# PWR.net
KiCad netlist of a schematic drawn in Altium Designer
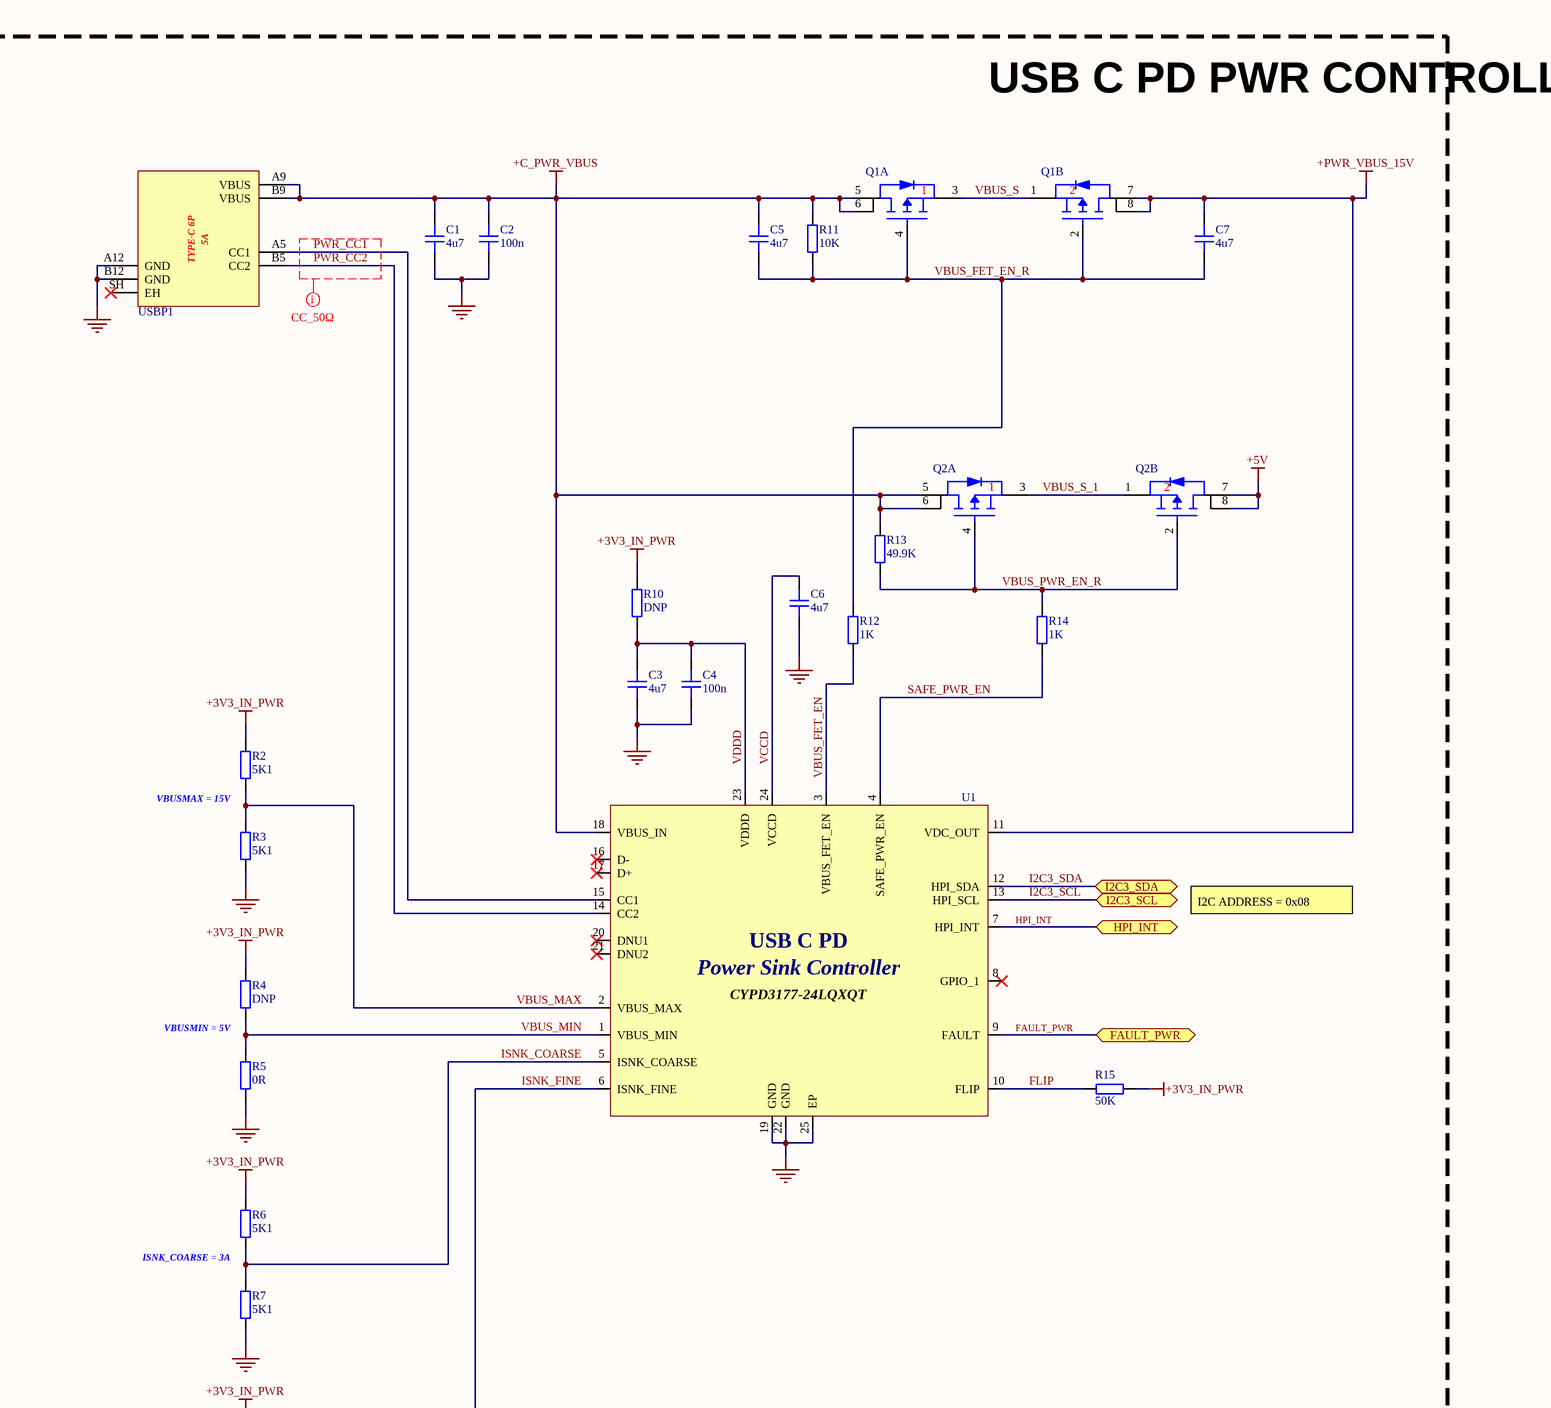
[diagram p0: PWR.SchDoc, top left]
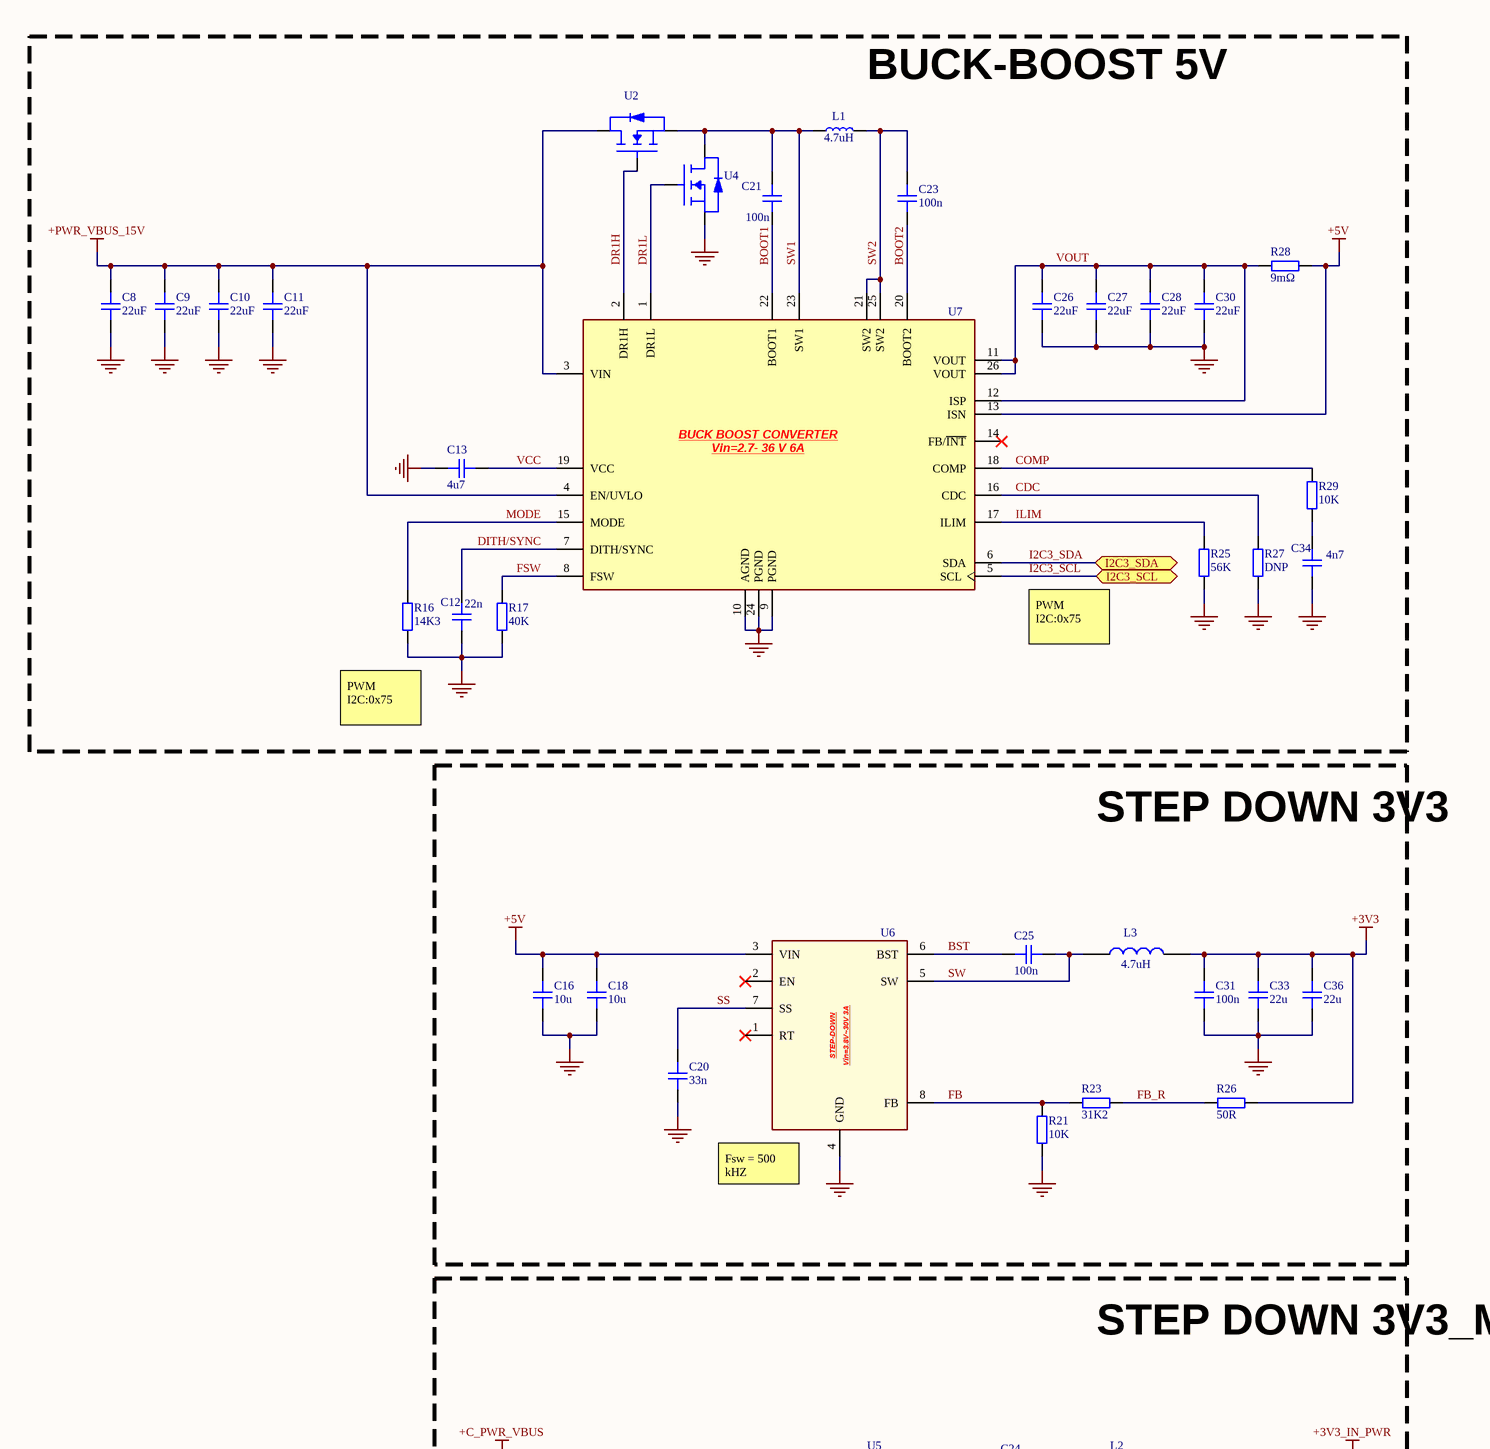
[diagram p1: PWR.SchDoc, top right]
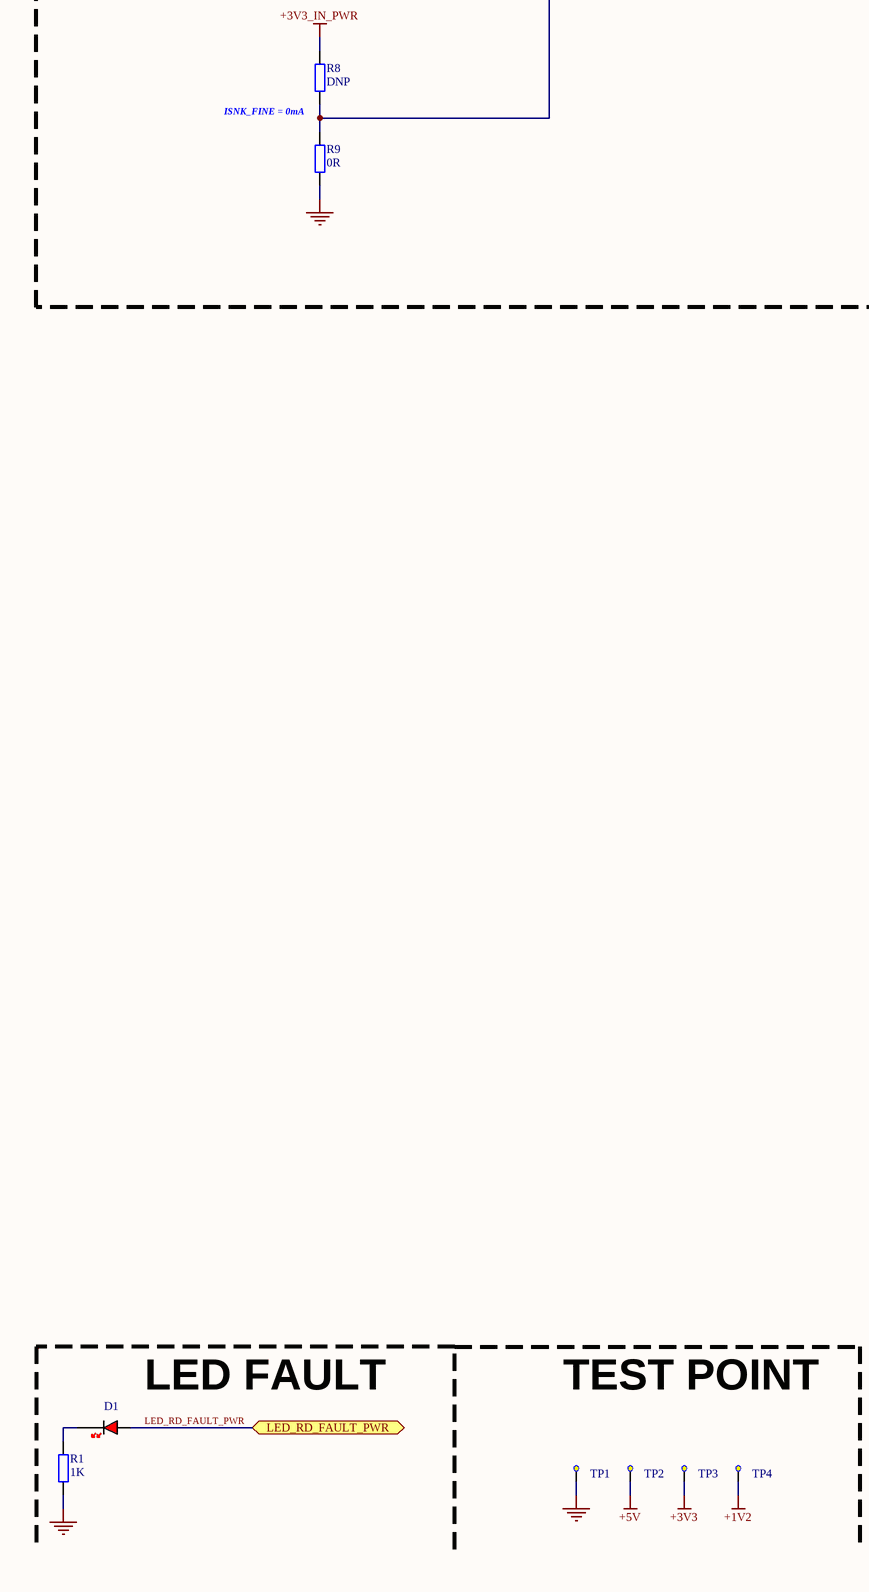
[diagram p2: PWR.SchDoc, bottom left]
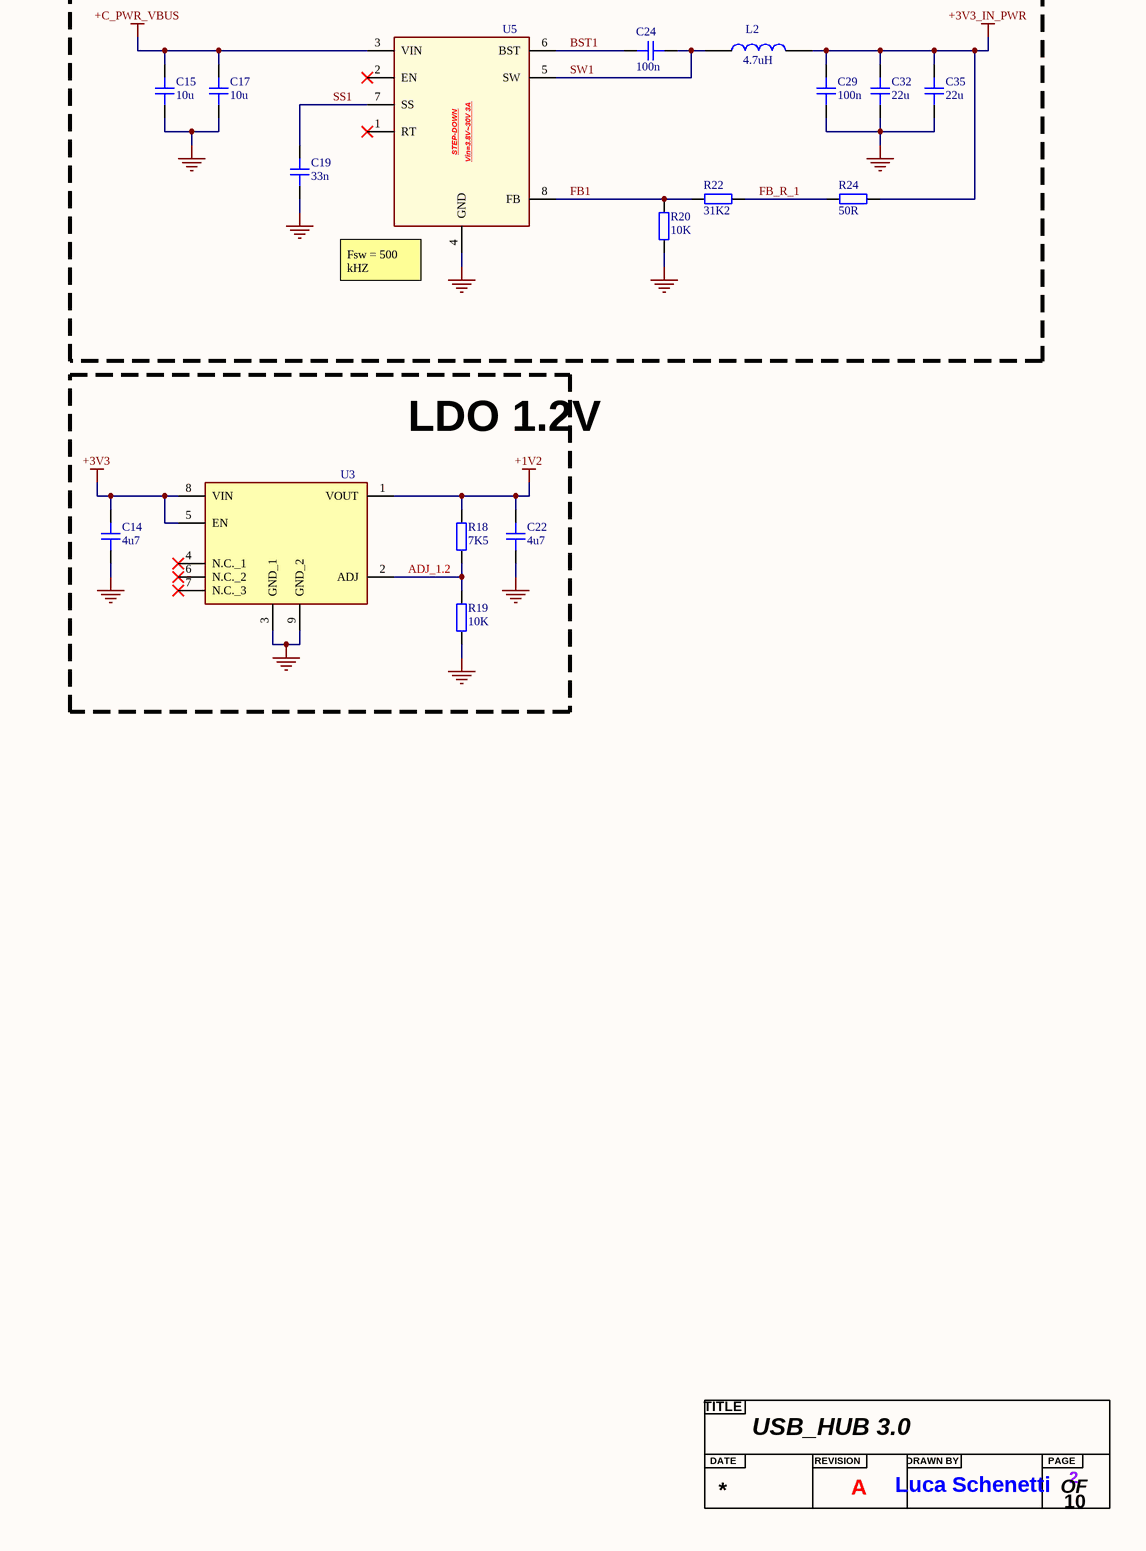
[diagram p3: PWR.SchDoc, bottom right]

(export (version "E")
  (design (tool "Eeschema 10.0.6"))
  (components
    (comp (ref "C1")
      (value "4u7")
      (footprint "CAP_0805")
      (description "[C1779]")
      (libsource (lib "Schematic-Lib-PhilsLab") (part "CAP_0805"))
    )
    (comp (ref "C2")
      (value "100n")
      (footprint "CAP_0603")
      (description "[C14663]")
      (libsource (lib "Schematic-Lib-PhilsLab") (part "CAP_0603"))
    )
    (comp (ref "C3")
      (value "4u7")
      (footprint "CAP_0603")
      (description "[C19666]")
      (libsource (lib "Schematic-Lib-PhilsLab") (part "CAP_0603"))
    )
    (comp (ref "C4")
      (value "100n")
      (footprint "CAP_0603")
      (description "[C14663]")
      (libsource (lib "Schematic-Lib-PhilsLab") (part "CAP_0603"))
    )
    (comp (ref "C5")
      (value "4u7")
      (footprint "CAP_0805")
      (description "[C1779]")
      (libsource (lib "Schematic-Lib-PhilsLab") (part "CAP_0805"))
    )
    (comp (ref "C6")
      (value "4u7")
      (footprint "CAP_0603")
      (description "[C69335]")
      (libsource (lib "Schematic-Lib-PhilsLab") (part "CAP_0603"))
    )
    (comp (ref "C7")
      (value "4u7")
      (footprint "CAP_0805")
      (description "[C1779]")
      (libsource (lib "Schematic-Lib-PhilsLab") (part "CAP_0805"))
    )
    (comp (ref "C8")
      (value "22uF")
      (footprint "CAP_0805")
      (description "[C45783]")
      (libsource (lib "Schematic-Lib-PhilsLab") (part "CAP_0805"))
    )
    (comp (ref "C9")
      (value "22uF")
      (footprint "CAP_0805")
      (description "[C45783]")
      (libsource (lib "Schematic-Lib-PhilsLab") (part "CAP_0805"))
    )
    (comp (ref "C10")
      (value "22uF")
      (footprint "CAP_0805")
      (description "[C45783]")
      (libsource (lib "Schematic-Lib-PhilsLab") (part "CAP_0805"))
    )
    (comp (ref "C11")
      (value "22uF")
      (footprint "CAP_0805")
      (description "[C45783]")
      (libsource (lib "Schematic-Lib-PhilsLab") (part "CAP_0805"))
    )
    (comp (ref "C12")
      (value "22n")
      (footprint "CAP_0603")
      (description "[C21122]")
      (libsource (lib "Schematic-Lib-PhilsLab") (part "CAP_0603"))
    )
    (comp (ref "C13")
      (value "4u7")
      (footprint "CAP_0603")
      (description "[C19666]")
      (libsource (lib "Schematic-Lib-PhilsLab") (part "CAP_0603"))
    )
    (comp (ref "C14")
      (value "4u7")
      (footprint "CAP_0603")
      (description "[C19666]")
      (libsource (lib "Schematic-Lib-PhilsLab") (part "CAP_0603"))
    )
    (comp (ref "C15")
      (value "10u")
      (footprint "CAP_0805")
      (description "Capacitor SMD 0805[C440198]")
      (libsource (lib "Schematic-Lib-PhilsLab") (part "CAP_0805"))
    )
    (comp (ref "C16")
      (value "10u")
      (footprint "CAP_0805")
      (description "Capacitor SMD 0805[C440198]")
      (libsource (lib "Schematic-Lib-PhilsLab") (part "CAP_0805"))
    )
    (comp (ref "C17")
      (value "10u")
      (footprint "CAP_0805")
      (description "Capacitor SMD 0805[C440198]")
      (libsource (lib "Schematic-Lib-PhilsLab") (part "CAP_0805"))
    )
    (comp (ref "C18")
      (value "10u")
      (footprint "CAP_0805")
      (description "Capacitor SMD 0805[C440198]")
      (libsource (lib "Schematic-Lib-PhilsLab") (part "CAP_0805"))
    )
    (comp (ref "C19")
      (value "33n")
      (footprint "CAP_0603")
      (description "[C21117]")
      (libsource (lib "Schematic-Lib-PhilsLab") (part "CAP_0603"))
    )
    (comp (ref "C20")
      (value "33n")
      (footprint "CAP_0603")
      (description "[C21117]")
      (libsource (lib "Schematic-Lib-PhilsLab") (part "CAP_0603"))
    )
    (comp (ref "C21")
      (value "100n")
      (footprint "CAP_0603")
      (description "[C14663]")
      (libsource (lib "Schematic-Lib-PhilsLab") (part "CAP_0603"))
    )
    (comp (ref "C22")
      (value "4u7")
      (footprint "CAP_0603")
      (description "[C19666]")
      (libsource (lib "Schematic-Lib-PhilsLab") (part "CAP_0603"))
    )
    (comp (ref "C23")
      (value "100n")
      (footprint "CAP_0603")
      (description "[C14663]")
      (libsource (lib "Schematic-Lib-PhilsLab") (part "CAP_0603"))
    )
    (comp (ref "C24")
      (value "100n")
      (footprint "CAP_0603")
      (description "Capacitor SMD 0603 [C14663]")
      (libsource (lib "Schematic-Lib-PhilsLab") (part "CAP_0603"))
    )
    (comp (ref "C25")
      (value "100n")
      (footprint "CAP_0603")
      (description "Capacitor SMD 0603 [C14663]")
      (libsource (lib "Schematic-Lib-PhilsLab") (part "CAP_0603"))
    )
    (comp (ref "C26")
      (value "22uF")
      (footprint "CAP_0805")
      (description "[C45783]")
      (libsource (lib "Schematic-Lib-PhilsLab") (part "CAP_0805"))
    )
    (comp (ref "C27")
      (value "22uF")
      (footprint "CAP_0805")
      (description "[C45783]")
      (libsource (lib "Schematic-Lib-PhilsLab") (part "CAP_0805"))
    )
    (comp (ref "C28")
      (value "22uF")
      (footprint "CAP_0805")
      (description "[C45783]")
      (libsource (lib "Schematic-Lib-PhilsLab") (part "CAP_0805"))
    )
    (comp (ref "C29")
      (value "100n")
      (footprint "CAP_0603")
      (description "Capacitor SMD 0603 [C14663]")
      (libsource (lib "Schematic-Lib-PhilsLab") (part "CAP_0603"))
    )
    (comp (ref "C30")
      (value "22uF")
      (footprint "CAP_0805")
      (description "[C45783]")
      (libsource (lib "Schematic-Lib-PhilsLab") (part "CAP_0805"))
    )
    (comp (ref "C31")
      (value "100n")
      (footprint "CAP_0603")
      (description "Capacitor SMD 0603 [C14663]")
      (libsource (lib "Schematic-Lib-PhilsLab") (part "CAP_0603"))
    )
    (comp (ref "C32")
      (value "22u")
      (footprint "CAP_0603")
      (description "Capacitor SMD 0603 [C59461]")
      (libsource (lib "Schematic-Lib-PhilsLab") (part "CAP_0603"))
    )
    (comp (ref "C33")
      (value "22u")
      (footprint "CAP_0603")
      (description "Capacitor SMD 0603 [C59461]")
      (libsource (lib "Schematic-Lib-PhilsLab") (part "CAP_0603"))
    )
    (comp (ref "C34")
      (value "4n7")
      (footprint "CAP_0603")
      (description "[C53987]")
      (libsource (lib "Schematic-Lib-PhilsLab") (part "CAP_0603"))
    )
    (comp (ref "C35")
      (value "22u")
      (footprint "CAP_0603")
      (description "Capacitor SMD 0603 [C59461]")
      (libsource (lib "Schematic-Lib-PhilsLab") (part "CAP_0603"))
    )
    (comp (ref "C36")
      (value "22u")
      (footprint "CAP_0603")
      (description "Capacitor SMD 0603 [C59461]")
      (libsource (lib "Schematic-Lib-PhilsLab") (part "CAP_0603"))
    )
    (comp (ref "D1")
      (value "RED")
      (footprint "LED_0603_RED")
      (description "LED 0603 RED SMD[C2926776]")
      (libsource (lib "Schematic-Lib-PhilsLab") (part "LED_0603_RED"))
    )
    (comp (ref "L1")
      (value "4.7uH")
      (footprint "XR0850-4R7M")
      (description "[C7498934]")
      (libsource (lib "My_Library") (part "XR0850-4R7M"))
    )
    (comp (ref "L2")
      (value "4.7uH")
      (footprint "FXL0530-4R7-M")
      (description "[C177246]")
      (libsource (lib "My_Library") (part "FXL0530-4R7-M"))
    )
    (comp (ref "L3")
      (value "4.7uH")
      (footprint "FXL0530-4R7-M")
      (description "[C177246]")
      (libsource (lib "My_Library") (part "FXL0530-4R7-M"))
    )
    (comp (ref "Q1")
      (value "AO4805")
      (footprint "SOIC-8")
      (description "[C5224317]")
      (fields (field (name "MANUFACTURER") "Alpha & Omega Semicon"))
      (libsource (lib "Schematic-Lib-PhilsLab") (part "AO4805"))
    )
    (comp (ref "Q2")
      (value "AO4805")
      (footprint "SOIC-8")
      (description "[C5224317]")
      (fields (field (name "MANUFACTURER") "Alpha & Omega Semicon"))
      (libsource (lib "Schematic-Lib-PhilsLab") (part "AO4805"))
    )
    (comp (ref "R1")
      (value "1K")
      (footprint "RES_0402")
      (description "[C11702]")
      (libsource (lib "Schematic-Lib-PhilsLab") (part "RES_0402"))
    )
    (comp (ref "R2")
      (value "5K1")
      (footprint "RES_0603")
      (description "[C23186]")
      (libsource (lib "Schematic-Lib-PhilsLab") (part "RES_0603"))
    )
    (comp (ref "R3")
      (value "5K1")
      (footprint "RES_0603")
      (description "[C23186]")
      (libsource (lib "Schematic-Lib-PhilsLab") (part "RES_0603"))
    )
    (comp (ref "R4")
      (value "DNP")
      (footprint "RES_0603")
      (libsource (lib "Schematic-Lib-PhilsLab") (part "RES_0603"))
    )
    (comp (ref "R5")
      (value "0R")
      (footprint "RES_0603")
      (description "[C21189]")
      (libsource (lib "Schematic-Lib-PhilsLab") (part "RES_0603"))
    )
    (comp (ref "R6")
      (value "5K1")
      (footprint "RES_0603")
      (description "[C23186]")
      (libsource (lib "Schematic-Lib-PhilsLab") (part "RES_0603"))
    )
    (comp (ref "R7")
      (value "5K1")
      (footprint "RES_0603")
      (description "[C23186]")
      (libsource (lib "Schematic-Lib-PhilsLab") (part "RES_0603"))
    )
    (comp (ref "R8")
      (value "DNP")
      (footprint "RES_0603")
      (libsource (lib "Schematic-Lib-PhilsLab") (part "RES_0603"))
    )
    (comp (ref "R9")
      (value "0R")
      (footprint "RES_0603")
      (description "[C21189]")
      (libsource (lib "Schematic-Lib-PhilsLab") (part "RES_0603"))
    )
    (comp (ref "R10")
      (value "DNP")
      (footprint "RES_0603")
      (libsource (lib "Schematic-Lib-PhilsLab") (part "RES_0603"))
    )
    (comp (ref "R11")
      (value "10K")
      (footprint "RES_0603")
      (description "[C25804]")
      (libsource (lib "Schematic-Lib-PhilsLab") (part "RES_0603"))
    )
    (comp (ref "R12")
      (value "1K")
      (footprint "RES_0603")
      (description "[C21190]")
      (libsource (lib "Schematic-Lib-PhilsLab") (part "RES_0603"))
    )
    (comp (ref "R13")
      (value "49.9K")
      (footprint "RES_0603")
      (description "[C23184]")
      (libsource (lib "Schematic-Lib-PhilsLab") (part "RES_0603"))
    )
    (comp (ref "R14")
      (value "1K")
      (footprint "RES_0603")
      (description "[C21190]")
      (libsource (lib "Schematic-Lib-PhilsLab") (part "RES_0603"))
    )
    (comp (ref "R15")
      (value "50K")
      (footprint "RES_0603")
      (description "[C861451]")
      (libsource (lib "Schematic-Lib-PhilsLab") (part "RES_0603"))
    )
    (comp (ref "R16")
      (value "14K3")
      (footprint "RES_0603")
      (description "[C2933145]")
      (libsource (lib "Schematic-Lib-PhilsLab") (part "RES_0603"))
    )
    (comp (ref "R17")
      (value "40K")
      (footprint "RES_0603")
      (description "[C3016445]")
      (libsource (lib "Schematic-Lib-PhilsLab") (part "RES_0603"))
    )
    (comp (ref "R18")
      (value "7K5")
      (footprint "RES_0603")
      (description "[C23234]")
      (libsource (lib "Schematic-Lib-PhilsLab") (part "RES_0603"))
    )
    (comp (ref "R19")
      (value "10K")
      (footprint "RES_0603")
      (description "[C25804]")
      (libsource (lib "Schematic-Lib-PhilsLab") (part "RES_0603"))
    )
    (comp (ref "R20")
      (value "10K")
      (footprint "RES_0603")
      (description "[C25804]")
      (libsource (lib "Schematic-Lib-PhilsLab") (part "RES_0603"))
    )
    (comp (ref "R21")
      (value "10K")
      (footprint "RES_0603")
      (description "[C25804]")
      (libsource (lib "Schematic-Lib-PhilsLab") (part "RES_0603"))
    )
    (comp (ref "R22")
      (value "31K2")
      (footprint "RES_0603")
      (description "[C863036]")
      (libsource (lib "Schematic-Lib-PhilsLab") (part "RES_0603"))
    )
    (comp (ref "R23")
      (value "31K2")
      (footprint "RES_0603")
      (description "[C863036]")
      (libsource (lib "Schematic-Lib-PhilsLab") (part "RES_0603"))
    )
    (comp (ref "R24")
      (value "50R")
      (footprint "RES_0603")
      (description "[C849792]")
      (libsource (lib "Schematic-Lib-PhilsLab") (part "RES_0603"))
    )
    (comp (ref "R25")
      (value "56K")
      (footprint "RES_0603")
      (description "[C23206]")
      (libsource (lib "Schematic-Lib-PhilsLab") (part "RES_0603"))
    )
    (comp (ref "R26")
      (value "50R")
      (footprint "RES_0603")
      (description "[C849792]")
      (libsource (lib "Schematic-Lib-PhilsLab") (part "RES_0603"))
    )
    (comp (ref "R27")
      (value "DNP")
      (footprint "RES_0603")
      (libsource (lib "Schematic-Lib-PhilsLab") (part "RES_0603"))
    )
    (comp (ref "R28")
      (value "9mΩ")
      (footprint "RES_1206")
      (description "[C2904216]")
      (libsource (lib "Schematic-Lib-PhilsLab") (part "RES_1206"))
    )
    (comp (ref "R29")
      (value "10K")
      (footprint "RES_0603")
      (description "[C25804]")
      (libsource (lib "Schematic-Lib-PhilsLab") (part "RES_0603"))
    )
    (comp (ref "TP1")
      (value "Test Point")
      (footprint "Test Point")
      (libsource (lib "My_Library") (part "Test Point"))
    )
    (comp (ref "TP2")
      (value "Test Point")
      (footprint "Test Point")
      (libsource (lib "My_Library") (part "Test Point"))
    )
    (comp (ref "TP3")
      (value "Test Point")
      (footprint "Test Point")
      (libsource (lib "My_Library") (part "Test Point"))
    )
    (comp (ref "TP4")
      (value "Test Point")
      (footprint "Test Point")
      (libsource (lib "My_Library") (part "Test Point"))
    )
    (comp (ref "U1")
      (value "Power Sink Controller")
      (footprint "CYPD3177-24LQXQT")
      (description "[C5904158]")
      (fields
        (field (name "MANUFACTURER") "Cypress Semicon")
        (field (name "MANUFACTURER PART NUMBER") "CYPD3177-24LQXQ")
      )
      (libsource (lib "My_Library") (part "CYPD3177-24LQXQT"))
    )
    (comp (ref "U2")
      (value "Mosfet N-Channel  Vgs=20V Id=48A")
      (footprint "AON6220")
      (description "[C2997886]")
      (libsource (lib "My_Library") (part "AON6220"))
    )
    (comp (ref "U3")
      (value "LDO ADJ 2A")
      (footprint "MD7672B50SF4")
      (description "[C920526]")
      (libsource (lib "My_Library") (part "MD7672B50SF4"))
    )
    (comp (ref "U4")
      (value "Mosfet N-Channel  Vgs=20V Id=48A")
      (footprint "AON6220")
      (description "[C2997886]")
      (libsource (lib "My_Library") (part "AON6220"))
    )
    (comp (ref "U5")
      (value "Step Down Converter 3A 3.8V~30V")
      (footprint "TPS62933DRLR")
      (description "[C3200405]")
      (libsource (lib "My_Library") (part "TPS62933DRLR"))
    )
    (comp (ref "U6")
      (value "Step Down Converter 3A 3.8V~30V")
      (footprint "TPS62933DRLR")
      (description "[C3200405]")
      (libsource (lib "My_Library") (part "TPS62933DRLR"))
    )
    (comp (ref "U7")
      (value "Buck-Boost Converter 6.35 A")
      (footprint "TPS55288RPMR")
      (description "[C2864583]")
      (libsource (lib "My_Library") (part "TPS55288RPMR"))
    )
    (comp (ref "USBP1")
      (value "USB Type-C 5A 6P")
      (footprint "USB-TYPE-C-009")
      (description "[C2927029]")
      (libsource (lib "My_Library") (part "USB-TYPE-C-009"))
    )
  )
  (nets
    (net (code "1") (name "+1V2") (class "Default")
      (node (ref "C22") (pin "2") (pinfunction "2_2") (pintype "passive"))
      (node (ref "R18") (pin "2") (pinfunction "2_2") (pintype "passive"))
      (node (ref "TP4") (pin "1") (pinfunction "Test_Point_1") (pintype "passive"))
      (node (ref "U3") (pin "1") (pinfunction "VOUT_1") (pintype "passive"))
    )
    (net (code "2") (name "+3V3") (class "Default")
      (node (ref "C14") (pin "2") (pinfunction "2_2") (pintype "passive"))
      (node (ref "C31") (pin "1") (pinfunction "1_1") (pintype "passive"))
      (node (ref "C33") (pin "2") (pinfunction "2_2") (pintype "passive"))
      (node (ref "C36") (pin "2") (pinfunction "2_2") (pintype "passive"))
      (node (ref "L3") (pin "2") (pinfunction "2_2") (pintype "passive"))
      (node (ref "R26") (pin "1") (pinfunction "1_1") (pintype "passive"))
      (node (ref "TP3") (pin "1") (pinfunction "Test_Point_1") (pintype "passive"))
      (node (ref "U3") (pin "5") (pinfunction "EN_5") (pintype "passive"))
      (node (ref "U3") (pin "8") (pinfunction "VIN_8") (pintype "passive"))
    )
    (net (code "3") (name "+3V3_IN_PWR") (class "Default")
      (node (ref "C29") (pin "1") (pinfunction "1_1") (pintype "passive"))
      (node (ref "C32") (pin "2") (pinfunction "2_2") (pintype "passive"))
      (node (ref "C35") (pin "2") (pinfunction "2_2") (pintype "passive"))
      (node (ref "L2") (pin "2") (pinfunction "2_2") (pintype "passive"))
      (node (ref "R10") (pin "2") (pinfunction "2_2") (pintype "passive"))
      (node (ref "R15") (pin "2") (pinfunction "2_2") (pintype "passive"))
      (node (ref "R2") (pin "2") (pinfunction "2_2") (pintype "passive"))
      (node (ref "R24") (pin "1") (pinfunction "1_1") (pintype "passive"))
      (node (ref "R4") (pin "2") (pinfunction "2_2") (pintype "passive"))
      (node (ref "R6") (pin "2") (pinfunction "2_2") (pintype "passive"))
      (node (ref "R8") (pin "2") (pinfunction "2_2") (pintype "passive"))
    )
    (net (code "4") (name "+5V") (class "Default")
      (node (ref "C16") (pin "2") (pinfunction "2_2") (pintype "passive"))
      (node (ref "C18") (pin "2") (pinfunction "2_2") (pintype "passive"))
      (node (ref "Q2") (pin "7") (pinfunction "D2_7") (pintype "passive"))
      (node (ref "Q2") (pin "8") (pinfunction "D2_8") (pintype "passive"))
      (node (ref "R28") (pin "2") (pinfunction "2_2") (pintype "passive"))
      (node (ref "TP2") (pin "1") (pinfunction "Test_Point_1") (pintype "passive"))
      (node (ref "U6") (pin "3") (pinfunction "VIN_3") (pintype "passive"))
      (node (ref "U7") (pin "13") (pinfunction "ISN_13") (pintype "passive"))
    )
    (net (code "5") (name "+C_PWR_VBUS") (class "Default")
      (node (ref "C1") (pin "2") (pinfunction "2_2") (pintype "passive"))
      (node (ref "C15") (pin "2") (pinfunction "2_2") (pintype "passive"))
      (node (ref "C17") (pin "2") (pinfunction "2_2") (pintype "passive"))
      (node (ref "C2") (pin "2") (pinfunction "2_2") (pintype "passive"))
      (node (ref "C5") (pin "2") (pinfunction "2_2") (pintype "passive"))
      (node (ref "Q1") (pin "5") (pinfunction "D1_5") (pintype "passive"))
      (node (ref "Q1") (pin "6") (pinfunction "D1_6") (pintype "passive"))
      (node (ref "Q2") (pin "5") (pinfunction "D1_5") (pintype "passive"))
      (node (ref "Q2") (pin "6") (pinfunction "D1_6") (pintype "passive"))
      (node (ref "R11") (pin "2") (pinfunction "2_2") (pintype "passive"))
      (node (ref "R13") (pin "2") (pinfunction "2_2") (pintype "passive"))
      (node (ref "U1") (pin "18") (pinfunction "VBUS_IN_18") (pintype "passive"))
      (node (ref "U5") (pin "3") (pinfunction "VIN_3") (pintype "passive"))
      (node (ref "USBP1") (pin "A9") (pinfunction "VBUS_A9") (pintype "passive"))
      (node (ref "USBP1") (pin "B9") (pinfunction "VBUS_B9") (pintype "passive"))
    )
    (net (code "6") (name "+PWR_VBUS_15V") (class "Default")
      (node (ref "C10") (pin "2") (pinfunction "2_2") (pintype "passive"))
      (node (ref "C11") (pin "2") (pinfunction "2_2") (pintype "passive"))
      (node (ref "C7") (pin "2") (pinfunction "2_2") (pintype "passive"))
      (node (ref "C8") (pin "2") (pinfunction "2_2") (pintype "passive"))
      (node (ref "C9") (pin "2") (pinfunction "2_2") (pintype "passive"))
      (node (ref "Q1") (pin "7") (pinfunction "D2_7") (pintype "passive"))
      (node (ref "Q1") (pin "8") (pinfunction "D2_8") (pintype "passive"))
      (node (ref "U1") (pin "11") (pinfunction "VDC_OUT_11") (pintype "passive"))
      (node (ref "U2") (pin "D") (pinfunction "D_D") (pintype "passive"))
      (node (ref "U7") (pin "3") (pinfunction "VIN_3") (pintype "passive"))
      (node (ref "U7") (pin "4") (pinfunction "EN/UVLO_4") (pintype "passive"))
    )
    (net (code "7") (name "/ADJ_1.2") (class "Default")
      (node (ref "R18") (pin "1") (pinfunction "1_1") (pintype "passive"))
      (node (ref "R19") (pin "2") (pinfunction "2_2") (pintype "passive"))
      (node (ref "U3") (pin "2") (pinfunction "ADJ_2") (pintype "passive"))
    )
    (net (code "8") (name "/BOOT1") (class "Default")
      (node (ref "C21") (pin "1") (pinfunction "1_1") (pintype "passive"))
      (node (ref "U7") (pin "22") (pinfunction "BOOT1_22") (pintype "passive"))
    )
    (net (code "9") (name "/BOOT2") (class "Default")
      (node (ref "C23") (pin "1") (pinfunction "1_1") (pintype "passive"))
      (node (ref "U7") (pin "20") (pinfunction "BOOT2_20") (pintype "passive"))
    )
    (net (code "10") (name "/BST") (class "Default")
      (node (ref "C25") (pin "2") (pinfunction "2_2") (pintype "passive"))
      (node (ref "U6") (pin "6") (pinfunction "BST_6") (pintype "passive"))
    )
    (net (code "11") (name "/BST1") (class "Default")
      (node (ref "C24") (pin "2") (pinfunction "2_2") (pintype "passive"))
      (node (ref "U5") (pin "6") (pinfunction "BST_6") (pintype "passive"))
    )
    (net (code "12") (name "/CDC") (class "Default")
      (node (ref "R27") (pin "2") (pinfunction "2_2") (pintype "passive"))
      (node (ref "U7") (pin "16") (pinfunction "CDC_16") (pintype "passive"))
    )
    (net (code "13") (name "/COMP") (class "Default")
      (node (ref "R29") (pin "2") (pinfunction "2_2") (pintype "passive"))
      (node (ref "U7") (pin "18") (pinfunction "COMP_18") (pintype "passive"))
    )
    (net (code "14") (name "/DITH{slash}SYNC") (class "Default")
      (node (ref "C12") (pin "2") (pinfunction "2_2") (pintype "passive"))
      (node (ref "U7") (pin "7") (pinfunction "DITH/SYNC_7") (pintype "passive"))
    )
    (net (code "15") (name "/DR1H") (class "Default")
      (node (ref "U2") (pin "G") (pinfunction "G_G") (pintype "passive"))
      (node (ref "U7") (pin "2") (pinfunction "DR1H_2") (pintype "passive"))
    )
    (net (code "16") (name "/DR1L") (class "Default")
      (node (ref "U4") (pin "G") (pinfunction "G_G") (pintype "passive"))
      (node (ref "U7") (pin "1") (pinfunction "DR1L_1") (pintype "passive"))
    )
    (net (code "17") (name "/FAULT_PWR") (class "Default")
      (node (ref "U1") (pin "9") (pinfunction "FAULT_9") (pintype "passive"))
    )
    (net (code "18") (name "/FB") (class "Default")
      (node (ref "R21") (pin "2") (pinfunction "2_2") (pintype "passive"))
      (node (ref "R23") (pin "2") (pinfunction "2_2") (pintype "passive"))
      (node (ref "U6") (pin "8") (pinfunction "FB_8") (pintype "passive"))
    )
    (net (code "19") (name "/FB1") (class "Default")
      (node (ref "R20") (pin "2") (pinfunction "2_2") (pintype "passive"))
      (node (ref "R22") (pin "2") (pinfunction "2_2") (pintype "passive"))
      (node (ref "U5") (pin "8") (pinfunction "FB_8") (pintype "passive"))
    )
    (net (code "20") (name "/FB_R") (class "Default")
      (node (ref "R23") (pin "1") (pinfunction "1_1") (pintype "passive"))
      (node (ref "R26") (pin "2") (pinfunction "2_2") (pintype "passive"))
    )
    (net (code "21") (name "/FB_R_1") (class "Default")
      (node (ref "R22") (pin "1") (pinfunction "1_1") (pintype "passive"))
      (node (ref "R24") (pin "2") (pinfunction "2_2") (pintype "passive"))
    )
    (net (code "22") (name "/FLIP") (class "Default")
      (node (ref "R15") (pin "1") (pinfunction "1_1") (pintype "passive"))
      (node (ref "U1") (pin "10") (pinfunction "FLIP_10") (pintype "passive"))
    )
    (net (code "23") (name "/FSW") (class "Default")
      (node (ref "R17") (pin "2") (pinfunction "2_2") (pintype "passive"))
      (node (ref "U7") (pin "8") (pinfunction "FSW_8") (pintype "passive"))
    )
    (net (code "24") (name "/HPI_INT") (class "Default")
      (node (ref "U1") (pin "7") (pinfunction "HPI_INT_7") (pintype "passive"))
    )
    (net (code "25") (name "/I2C3_SCL") (class "Default")
      (node (ref "U1") (pin "13") (pinfunction "HPI_SCL_13") (pintype "passive"))
      (node (ref "U7") (pin "5") (pinfunction "SCL_5") (pintype "passive"))
    )
    (net (code "26") (name "/I2C3_SDA") (class "Default")
      (node (ref "U1") (pin "12") (pinfunction "HPI_SDA_12") (pintype "passive"))
      (node (ref "U7") (pin "6") (pinfunction "SDA_6") (pintype "passive"))
    )
    (net (code "27") (name "/ILIM") (class "Default")
      (node (ref "R25") (pin "2") (pinfunction "2_2") (pintype "passive"))
      (node (ref "U7") (pin "17") (pinfunction "ILIM_17") (pintype "passive"))
    )
    (net (code "28") (name "/ISNK_COARSE") (class "Default")
      (node (ref "R6") (pin "1") (pinfunction "1_1") (pintype "passive"))
      (node (ref "R7") (pin "2") (pinfunction "2_2") (pintype "passive"))
      (node (ref "U1") (pin "5") (pinfunction "ISNK_COARSE_5") (pintype "passive"))
    )
    (net (code "29") (name "/ISNK_FINE") (class "Default")
      (node (ref "R8") (pin "1") (pinfunction "1_1") (pintype "passive"))
      (node (ref "R9") (pin "2") (pinfunction "2_2") (pintype "passive"))
      (node (ref "U1") (pin "6") (pinfunction "ISNK_FINE_6") (pintype "passive"))
    )
    (net (code "30") (name "/LED_RD_FAULT_PWR") (class "Default")
      (node (ref "D1") (pin "A") (pinfunction "A_A") (pintype "passive"))
    )
    (net (code "31") (name "/MODE") (class "Default")
      (node (ref "R16") (pin "2") (pinfunction "2_2") (pintype "passive"))
      (node (ref "U7") (pin "15") (pinfunction "MODE_15") (pintype "passive"))
    )
    (net (code "32") (name "/PWR_CC1") (class "Default")
      (node (ref "U1") (pin "15") (pinfunction "CC1_15") (pintype "passive"))
      (node (ref "USBP1") (pin "A5") (pinfunction "CC1_A5") (pintype "passive"))
    )
    (net (code "33") (name "/PWR_CC2") (class "Default")
      (node (ref "U1") (pin "14") (pinfunction "CC2_14") (pintype "passive"))
      (node (ref "USBP1") (pin "B5") (pinfunction "CC2_B5") (pintype "passive"))
    )
    (net (code "34") (name "/SAFE_PWR_EN") (class "Default")
      (node (ref "R14") (pin "1") (pinfunction "1_1") (pintype "passive"))
      (node (ref "U1") (pin "4") (pinfunction "SAFE_PWR_EN_4") (pintype "passive"))
    )
    (net (code "35") (name "/SS") (class "Default")
      (node (ref "C20") (pin "1") (pinfunction "1_1") (pintype "passive"))
      (node (ref "U6") (pin "7") (pinfunction "SS_7") (pintype "passive"))
    )
    (net (code "36") (name "/SS1") (class "Default")
      (node (ref "C19") (pin "1") (pinfunction "1_1") (pintype "passive"))
      (node (ref "U5") (pin "7") (pinfunction "SS_7") (pintype "passive"))
    )
    (net (code "37") (name "/SW") (class "Default")
      (node (ref "C25") (pin "1") (pinfunction "1_1") (pintype "passive"))
      (node (ref "L3") (pin "1") (pinfunction "1_1") (pintype "passive"))
      (node (ref "U6") (pin "5") (pinfunction "SW_5") (pintype "passive"))
    )
    (net (code "38") (name "/SW1") (class "Default")
      (node (ref "C21") (pin "2") (pinfunction "2_2") (pintype "passive"))
      (node (ref "C24") (pin "1") (pinfunction "1_1") (pintype "passive"))
      (node (ref "L1") (pin "1") (pinfunction "1_1") (pintype "passive"))
      (node (ref "L2") (pin "1") (pinfunction "1_1") (pintype "passive"))
      (node (ref "U2") (pin "S") (pinfunction "S_S") (pintype "passive"))
      (node (ref "U4") (pin "D") (pinfunction "D_D") (pintype "passive"))
      (node (ref "U5") (pin "5") (pinfunction "SW_5") (pintype "passive"))
      (node (ref "U7") (pin "23") (pinfunction "SW1_23") (pintype "passive"))
    )
    (net (code "39") (name "/SW2") (class "Default")
      (node (ref "C23") (pin "2") (pinfunction "2_2") (pintype "passive"))
      (node (ref "L1") (pin "2") (pinfunction "2_2") (pintype "passive"))
      (node (ref "U7") (pin "21") (pinfunction "SW2_21") (pintype "passive"))
      (node (ref "U7") (pin "25") (pinfunction "SW2_25") (pintype "passive"))
    )
    (net (code "40") (name "/VBUS_FET_EN") (class "Default")
      (node (ref "R12") (pin "1") (pinfunction "1_1") (pintype "passive"))
      (node (ref "U1") (pin "3") (pinfunction "VBUS_FET_EN_3") (pintype "passive"))
    )
    (net (code "41") (name "/VBUS_FET_EN_R") (class "Default")
      (node (ref "C5") (pin "1") (pinfunction "1_1") (pintype "passive"))
      (node (ref "C7") (pin "1") (pinfunction "1_1") (pintype "passive"))
      (node (ref "Q1") (pin "2") (pinfunction "G2_2") (pintype "passive"))
      (node (ref "Q1") (pin "4") (pinfunction "G1_4") (pintype "passive"))
      (node (ref "R11") (pin "1") (pinfunction "1_1") (pintype "passive"))
      (node (ref "R12") (pin "2") (pinfunction "2_2") (pintype "passive"))
    )
    (net (code "42") (name "/VBUS_MAX") (class "Default")
      (node (ref "R2") (pin "1") (pinfunction "1_1") (pintype "passive"))
      (node (ref "R3") (pin "2") (pinfunction "2_2") (pintype "passive"))
      (node (ref "U1") (pin "2") (pinfunction "VBUS_MAX_2") (pintype "passive"))
    )
    (net (code "43") (name "/VBUS_MIN") (class "Default")
      (node (ref "R4") (pin "1") (pinfunction "1_1") (pintype "passive"))
      (node (ref "R5") (pin "2") (pinfunction "2_2") (pintype "passive"))
      (node (ref "U1") (pin "1") (pinfunction "VBUS_MIN_1") (pintype "passive"))
    )
    (net (code "44") (name "/VBUS_PWR_EN_R") (class "Default")
      (node (ref "Q2") (pin "2") (pinfunction "G2_2") (pintype "passive"))
      (node (ref "Q2") (pin "4") (pinfunction "G1_4") (pintype "passive"))
      (node (ref "R13") (pin "1") (pinfunction "1_1") (pintype "passive"))
      (node (ref "R14") (pin "2") (pinfunction "2_2") (pintype "passive"))
    )
    (net (code "45") (name "/VBUS_S") (class "Default")
      (node (ref "Q1") (pin "1") (pinfunction "S2_1") (pintype "passive"))
      (node (ref "Q1") (pin "3") (pinfunction "S1_3") (pintype "passive"))
    )
    (net (code "46") (name "/VBUS_S_1") (class "Default")
      (node (ref "Q2") (pin "1") (pinfunction "S2_1") (pintype "passive"))
      (node (ref "Q2") (pin "3") (pinfunction "S1_3") (pintype "passive"))
    )
    (net (code "47") (name "/VCC") (class "Default")
      (node (ref "C13") (pin "1") (pinfunction "1_1") (pintype "passive"))
      (node (ref "U7") (pin "19") (pinfunction "VCC_19") (pintype "passive"))
    )
    (net (code "48") (name "/VCCD") (class "Default")
      (node (ref "C6") (pin "2") (pinfunction "2_2") (pintype "passive"))
      (node (ref "U1") (pin "24") (pinfunction "VCCD_24") (pintype "passive"))
    )
    (net (code "49") (name "/VDDD") (class "Default")
      (node (ref "C3") (pin "2") (pinfunction "2_2") (pintype "passive"))
      (node (ref "C4") (pin "2") (pinfunction "2_2") (pintype "passive"))
      (node (ref "R10") (pin "1") (pinfunction "1_1") (pintype "passive"))
      (node (ref "U1") (pin "23") (pinfunction "VDDD_23") (pintype "passive"))
    )
    (net (code "50") (name "/VOUT") (class "Default")
      (node (ref "C26") (pin "2") (pinfunction "2_2") (pintype "passive"))
      (node (ref "C27") (pin "2") (pinfunction "2_2") (pintype "passive"))
      (node (ref "C28") (pin "2") (pinfunction "2_2") (pintype "passive"))
      (node (ref "C30") (pin "2") (pinfunction "2_2") (pintype "passive"))
      (node (ref "R28") (pin "1") (pinfunction "1_1") (pintype "passive"))
      (node (ref "U7") (pin "11") (pinfunction "VOUT_11") (pintype "passive"))
      (node (ref "U7") (pin "12") (pinfunction "ISP_12") (pintype "passive"))
      (node (ref "U7") (pin "26") (pinfunction "VOUT_26") (pintype "passive"))
    )
    (net (code "51") (name "GND") (class "Default")
      (node (ref "C1") (pin "1") (pinfunction "1_1") (pintype "passive"))
      (node (ref "C10") (pin "1") (pinfunction "1_1") (pintype "passive"))
      (node (ref "C11") (pin "1") (pinfunction "1_1") (pintype "passive"))
      (node (ref "C12") (pin "1") (pinfunction "1_1") (pintype "passive"))
      (node (ref "C13") (pin "2") (pinfunction "2_2") (pintype "passive"))
      (node (ref "C14") (pin "1") (pinfunction "1_1") (pintype "passive"))
      (node (ref "C15") (pin "1") (pinfunction "1_1") (pintype "passive"))
      (node (ref "C16") (pin "1") (pinfunction "1_1") (pintype "passive"))
      (node (ref "C17") (pin "1") (pinfunction "1_1") (pintype "passive"))
      (node (ref "C18") (pin "1") (pinfunction "1_1") (pintype "passive"))
      (node (ref "C19") (pin "2") (pinfunction "2_2") (pintype "passive"))
      (node (ref "C2") (pin "1") (pinfunction "1_1") (pintype "passive"))
      (node (ref "C20") (pin "2") (pinfunction "2_2") (pintype "passive"))
      (node (ref "C22") (pin "1") (pinfunction "1_1") (pintype "passive"))
      (node (ref "C26") (pin "1") (pinfunction "1_1") (pintype "passive"))
      (node (ref "C27") (pin "1") (pinfunction "1_1") (pintype "passive"))
      (node (ref "C28") (pin "1") (pinfunction "1_1") (pintype "passive"))
      (node (ref "C29") (pin "2") (pinfunction "2_2") (pintype "passive"))
      (node (ref "C3") (pin "1") (pinfunction "1_1") (pintype "passive"))
      (node (ref "C30") (pin "1") (pinfunction "1_1") (pintype "passive"))
      (node (ref "C31") (pin "2") (pinfunction "2_2") (pintype "passive"))
      (node (ref "C32") (pin "1") (pinfunction "1_1") (pintype "passive"))
      (node (ref "C33") (pin "1") (pinfunction "1_1") (pintype "passive"))
      (node (ref "C34") (pin "1") (pinfunction "1_1") (pintype "passive"))
      (node (ref "C35") (pin "1") (pinfunction "1_1") (pintype "passive"))
      (node (ref "C36") (pin "1") (pinfunction "1_1") (pintype "passive"))
      (node (ref "C4") (pin "1") (pinfunction "1_1") (pintype "passive"))
      (node (ref "C6") (pin "1") (pinfunction "1_1") (pintype "passive"))
      (node (ref "C8") (pin "1") (pinfunction "1_1") (pintype "passive"))
      (node (ref "C9") (pin "1") (pinfunction "1_1") (pintype "passive"))
      (node (ref "R1") (pin "1") (pinfunction "1_1") (pintype "passive"))
      (node (ref "R16") (pin "1") (pinfunction "1_1") (pintype "passive"))
      (node (ref "R17") (pin "1") (pinfunction "1_1") (pintype "passive"))
      (node (ref "R19") (pin "1") (pinfunction "1_1") (pintype "passive"))
      (node (ref "R20") (pin "1") (pinfunction "1_1") (pintype "passive"))
      (node (ref "R21") (pin "1") (pinfunction "1_1") (pintype "passive"))
      (node (ref "R25") (pin "1") (pinfunction "1_1") (pintype "passive"))
      (node (ref "R27") (pin "1") (pinfunction "1_1") (pintype "passive"))
      (node (ref "R3") (pin "1") (pinfunction "1_1") (pintype "passive"))
      (node (ref "R5") (pin "1") (pinfunction "1_1") (pintype "passive"))
      (node (ref "R7") (pin "1") (pinfunction "1_1") (pintype "passive"))
      (node (ref "R9") (pin "1") (pinfunction "1_1") (pintype "passive"))
      (node (ref "TP1") (pin "1") (pinfunction "Test_Point_1") (pintype "passive"))
      (node (ref "U1") (pin "19") (pinfunction "GND_19") (pintype "power_in"))
      (node (ref "U1") (pin "22") (pinfunction "GND_22") (pintype "power_in"))
      (node (ref "U1") (pin "25") (pinfunction "EP_25") (pintype "power_in"))
      (node (ref "U3") (pin "3") (pinfunction "GND_1_3") (pintype "passive"))
      (node (ref "U3") (pin "9") (pinfunction "GND_2_9") (pintype "passive"))
      (node (ref "U4") (pin "S") (pinfunction "S_S") (pintype "passive"))
      (node (ref "U5") (pin "4") (pinfunction "GND_4") (pintype "power_in"))
      (node (ref "U6") (pin "4") (pinfunction "GND_4") (pintype "power_in"))
      (node (ref "U7") (pin "10") (pinfunction "AGND_10") (pintype "power_in"))
      (node (ref "U7") (pin "24") (pinfunction "PGND_24") (pintype "power_in"))
      (node (ref "U7") (pin "9") (pinfunction "PGND_9") (pintype "power_in"))
      (node (ref "USBP1") (pin "A12") (pinfunction "GND_A12") (pintype "passive"))
      (node (ref "USBP1") (pin "B12") (pinfunction "GND_B12") (pintype "passive"))
    )
    (net (code "52") (name "Net-(C34-Pad2)") (class "Default")
      (node (ref "C34") (pin "2") (pinfunction "2_2") (pintype "passive"))
      (node (ref "R29") (pin "1") (pinfunction "1_1") (pintype "passive"))
    )
    (net (code "53") (name "Net-(D1-PadK)") (class "Default")
      (node (ref "D1") (pin "K") (pinfunction "K_K") (pintype "passive"))
      (node (ref "R1") (pin "2") (pinfunction "2_2") (pintype "passive"))
    )
    (net (code "54") (name "unconnected-(U1-D+-Pad17)") (class "Default")
      (node (ref "U1") (pin "17") (pinfunction "D+_17") (pintype "passive+no_connect"))
    )
    (net (code "55") (name "unconnected-(U1-D--Pad16)") (class "Default")
      (node (ref "U1") (pin "16") (pinfunction "D-_16") (pintype "passive+no_connect"))
    )
    (net (code "56") (name "unconnected-(U1-DNU1-Pad20)") (class "Default")
      (node (ref "U1") (pin "20") (pinfunction "DNU1_20") (pintype "passive+no_connect"))
    )
    (net (code "57") (name "unconnected-(U1-DNU2-Pad21)") (class "Default")
      (node (ref "U1") (pin "21") (pinfunction "DNU2_21") (pintype "passive+no_connect"))
    )
    (net (code "58") (name "unconnected-(U1-GPIO_1-Pad8)") (class "Default")
      (node (ref "U1") (pin "8") (pinfunction "GPIO_1_8") (pintype "passive+no_connect"))
    )
    (net (code "59") (name "unconnected-(U3-N.C._1-Pad4)") (class "Default")
      (node (ref "U3") (pin "4") (pinfunction "N.C._1_4") (pintype "passive+no_connect"))
    )
    (net (code "60") (name "unconnected-(U3-N.C._2-Pad6)") (class "Default")
      (node (ref "U3") (pin "6") (pinfunction "N.C._2_6") (pintype "passive+no_connect"))
    )
    (net (code "61") (name "unconnected-(U3-N.C._3-Pad7)") (class "Default")
      (node (ref "U3") (pin "7") (pinfunction "N.C._3_7") (pintype "passive+no_connect"))
    )
    (net (code "62") (name "unconnected-(U5-EN-Pad2)") (class "Default")
      (node (ref "U5") (pin "2") (pinfunction "EN_2") (pintype "passive+no_connect"))
    )
    (net (code "63") (name "unconnected-(U5-RT-Pad1)") (class "Default")
      (node (ref "U5") (pin "1") (pinfunction "RT_1") (pintype "passive+no_connect"))
    )
    (net (code "64") (name "unconnected-(U6-EN-Pad2)") (class "Default")
      (node (ref "U6") (pin "2") (pinfunction "EN_2") (pintype "passive+no_connect"))
    )
    (net (code "65") (name "unconnected-(U6-RT-Pad1)") (class "Default")
      (node (ref "U6") (pin "1") (pinfunction "RT_1") (pintype "passive+no_connect"))
    )
    (net (code "66") (name "unconnected-(U7-FB{slash}~{INT}-Pad14)") (class "Default")
      (node (ref "U7") (pin "14") (pinfunction "FB/~{INT}_14") (pintype "passive+no_connect"))
    )
    (net (code "67") (name "unconnected-(USBP1-EH-PadSH)") (class "Default")
      (node (ref "USBP1") (pin "SH") (pinfunction "EH_SH") (pintype "passive+no_connect"))
    )
  )
)
